# powersupply_vol6.net
KiCad netlist of a schematic drawn in EAGLE
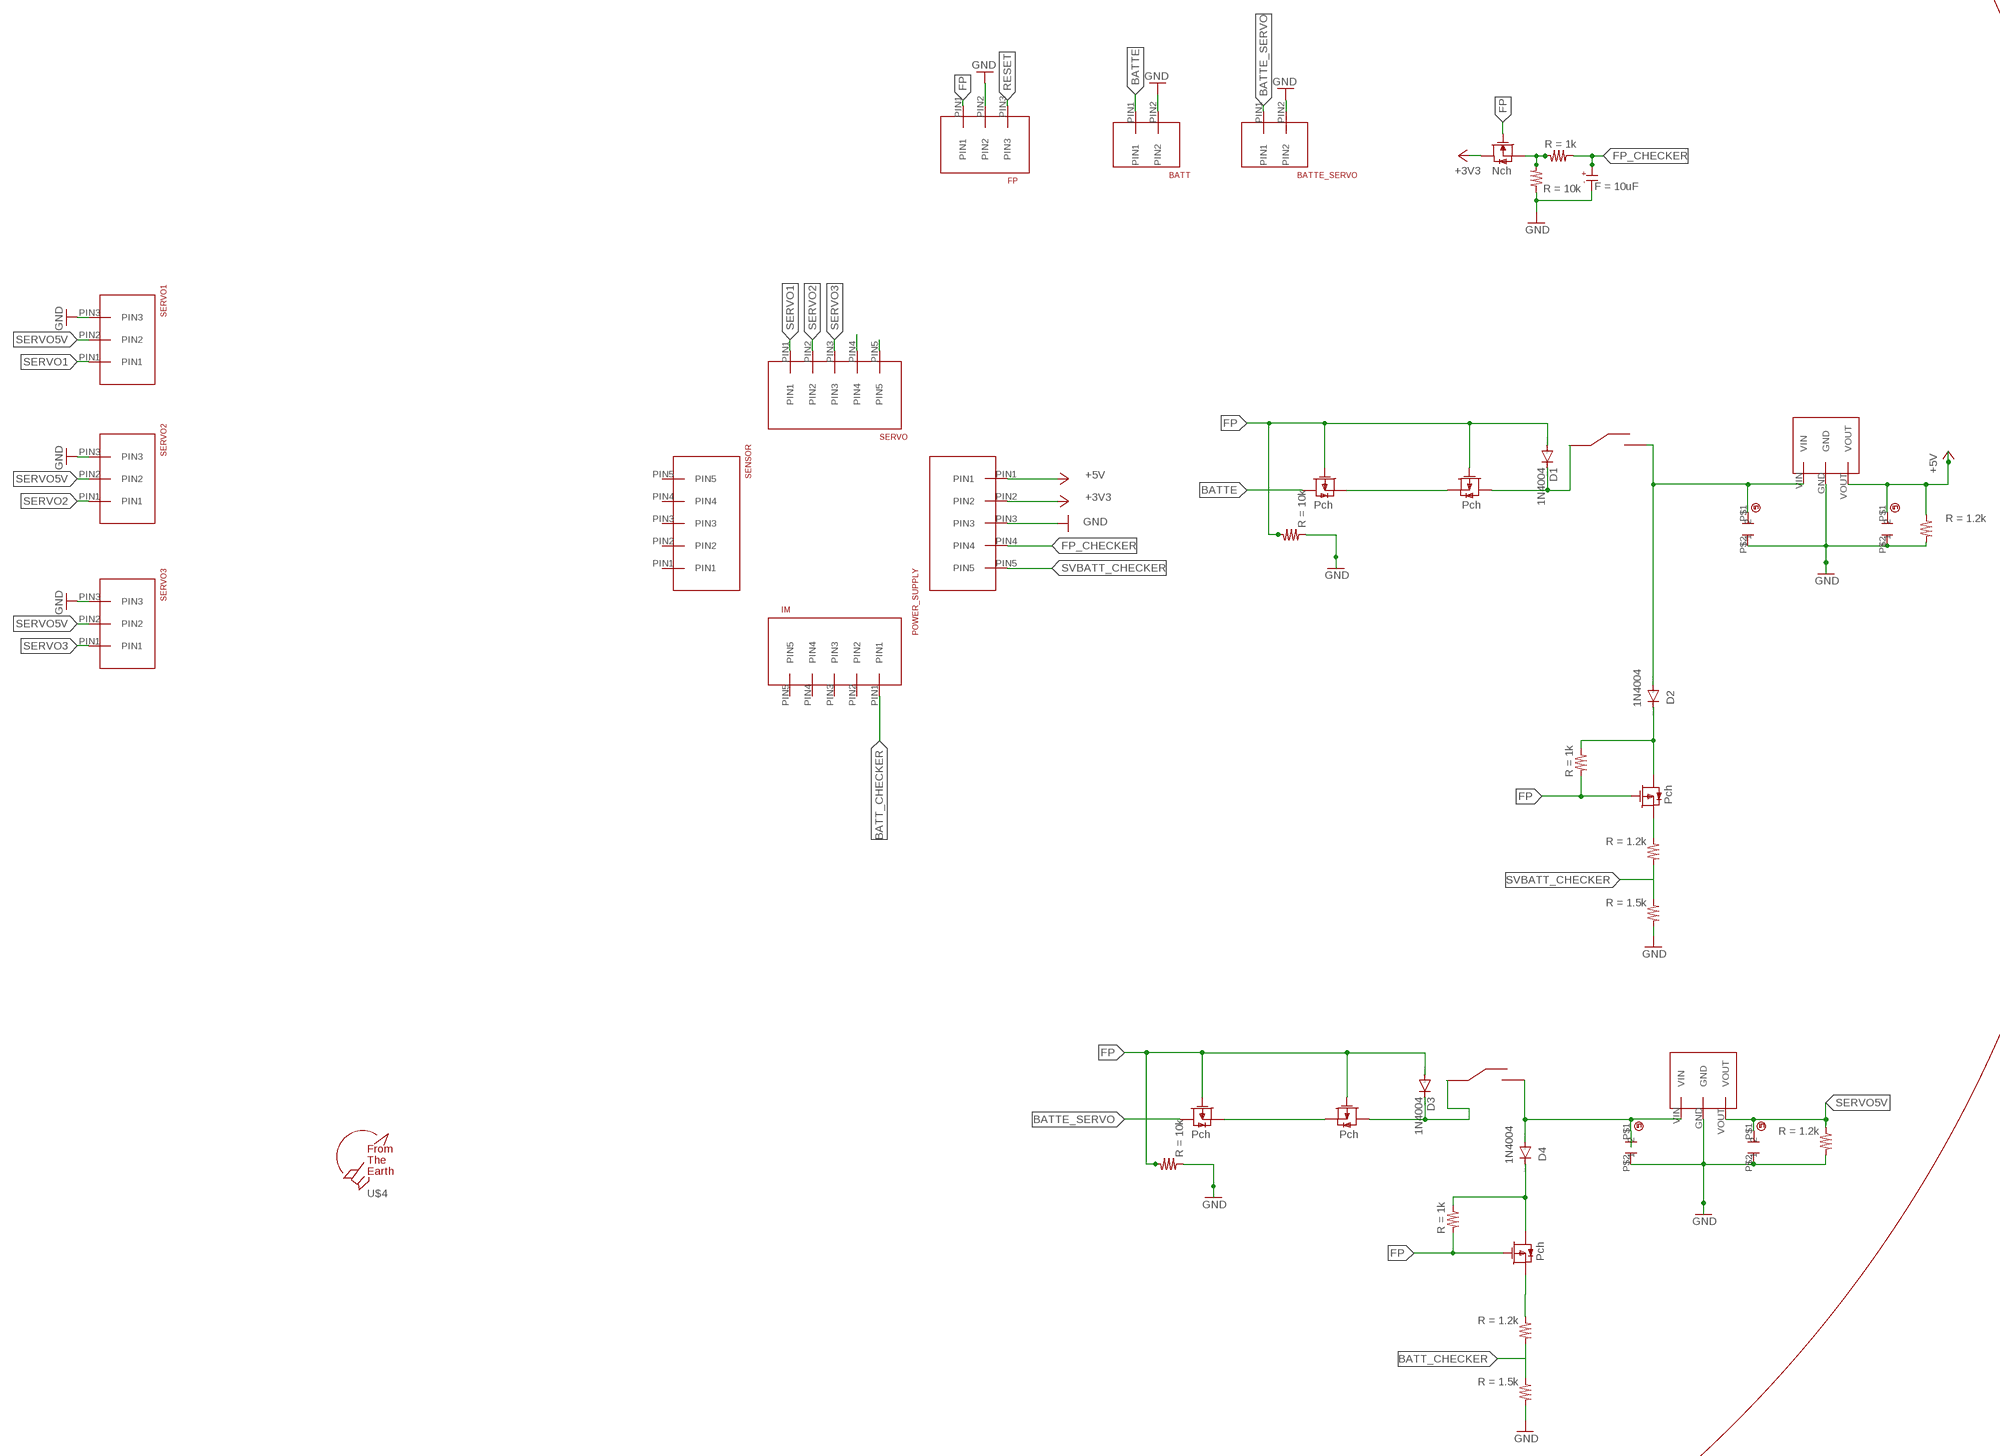
[diagram p0: schematic, sheet 1]

(export (version "E")
  (design (tool "Eeschema 10.0.6"))
  (components
    (comp (ref "BATT")
      (value "2PIN")
      (footprint "eagle-import:2PIN")
      (libsource (lib "eagle-import") (part "2PIN"))
    )
    (comp (ref "BATTE_SERVO")
      (value "2PIN")
      (footprint "eagle-import:2PIN")
      (libsource (lib "eagle-import") (part "2PIN"))
    )
    (comp (ref "C1")
      (value "CAPACITOR-ELECTROLYTIC_1")
      (footprint "eagle-import:CAPACITOR-ELECTROLYTIC_1")
      (fields (field (name "F") "10uF"))
      (libsource (lib "eagle-import") (part "CAPACITOR-ELECTROLYTIC_1"))
    )
    (comp (ref "CERAMIC_CAPACITOR3")
      (value "CERAMIC_CAPACITOR")
      (footprint "eagle-import:CERAMIC_CAPACITOR")
      (libsource (lib "eagle-import") (part "CERAMIC_CAPACITOR"))
    )
    (comp (ref "CERAMIC_CAPACITOR4")
      (value "CERAMIC_CAPACITOR")
      (footprint "eagle-import:CERAMIC_CAPACITOR")
      (libsource (lib "eagle-import") (part "CERAMIC_CAPACITOR"))
    )
    (comp (ref "CERAMIC_CAPACITOR5")
      (value "CERAMIC_CAPACITOR")
      (footprint "eagle-import:CERAMIC_CAPACITOR")
      (libsource (lib "eagle-import") (part "CERAMIC_CAPACITOR"))
    )
    (comp (ref "CERAMIC_CAPACITOR6")
      (value "CERAMIC_CAPACITOR")
      (footprint "eagle-import:CERAMIC_CAPACITOR")
      (libsource (lib "eagle-import") (part "CERAMIC_CAPACITOR"))
    )
    (comp (ref "D1")
      (value "1N4004")
      (footprint "eagle-import:DO41-10")
      (libsource (lib "eagle-import") (part "1N4004"))
    )
    (comp (ref "D2")
      (value "1N4004")
      (footprint "eagle-import:DO41-10")
      (libsource (lib "eagle-import") (part "1N4004"))
    )
    (comp (ref "D3")
      (value "1N4004")
      (footprint "eagle-import:DO41-10")
      (libsource (lib "eagle-import") (part "1N4004"))
    )
    (comp (ref "D4")
      (value "1N4004")
      (footprint "eagle-import:DO41-10")
      (libsource (lib "eagle-import") (part "1N4004"))
    )
    (comp (ref "FP")
      (value "3PIN")
      (footprint "eagle-import:3PIN")
      (libsource (lib "eagle-import") (part "3PIN"))
    )
    (comp (ref "IM")
      (value "5PIN")
      (footprint "eagle-import:5PIN")
      (libsource (lib "eagle-import") (part "5PIN"))
    )
    (comp (ref "POWER_SUPPLY")
      (value "5PIN")
      (footprint "eagle-import:5PIN")
      (libsource (lib "eagle-import") (part "5PIN"))
    )
    (comp (ref "R1")
      (value "1.5k")
      (footprint "eagle-import:REGISTER")
      (fields (field (name "R") "1.5k"))
      (libsource (lib "eagle-import") (part "RESISTER"))
    )
    (comp (ref "R2")
      (value "RESISTER")
      (footprint "eagle-import:REGISTER")
      (fields (field (name "R") "10k"))
      (libsource (lib "eagle-import") (part "RESISTER"))
    )
    (comp (ref "R3")
      (value "RESISTER")
      (footprint "eagle-import:REGISTER")
      (fields (field (name "R") "1.2k"))
      (libsource (lib "eagle-import") (part "RESISTER"))
    )
    (comp (ref "R4")
      (value "1.5k")
      (footprint "eagle-import:REGISTER")
      (fields (field (name "R") "1.5k"))
      (libsource (lib "eagle-import") (part "RESISTER"))
    )
    (comp (ref "R5")
      (value "RESISTER")
      (footprint "eagle-import:REGISTER")
      (fields (field (name "R") "10k"))
      (libsource (lib "eagle-import") (part "RESISTER"))
    )
    (comp (ref "R6")
      (value "RESISTER")
      (footprint "eagle-import:REGISTER")
      (fields (field (name "R") "1.2k"))
      (libsource (lib "eagle-import") (part "RESISTER"))
    )
    (comp (ref "R7")
      (value "RESISTER")
      (footprint "eagle-import:REGISTER")
      (fields (field (name "R") "1k"))
      (libsource (lib "eagle-import") (part "RESISTER"))
    )
    (comp (ref "R8")
      (value "RESISTER")
      (footprint "eagle-import:REGISTER")
      (fields (field (name "R") "1k"))
      (libsource (lib "eagle-import") (part "RESISTER"))
    )
    (comp (ref "R9")
      (value "RESISTER")
      (footprint "eagle-import:REGISTER")
      (fields (field (name "R") "10k"))
      (libsource (lib "eagle-import") (part "RESISTER"))
    )
    (comp (ref "R10")
      (value "RESISTER")
      (footprint "eagle-import:REGISTER")
      (fields (field (name "R") "1k"))
      (libsource (lib "eagle-import") (part "RESISTER"))
    )
    (comp (ref "R11")
      (value "RESISTER")
      (footprint "eagle-import:REGISTER")
      (fields (field (name "R") "1.2k"))
      (libsource (lib "eagle-import") (part "RESISTER"))
    )
    (comp (ref "R12")
      (value "RESISTER")
      (footprint "eagle-import:REGISTER")
      (fields (field (name "R") "1.2k"))
      (libsource (lib "eagle-import") (part "RESISTER"))
    )
    (comp (ref "SENSOR")
      (value "5PIN")
      (footprint "eagle-import:5PIN")
      (libsource (lib "eagle-import") (part "5PIN"))
    )
    (comp (ref "SERVO")
      (value "5PIN")
      (footprint "eagle-import:5PIN")
      (libsource (lib "eagle-import") (part "5PIN"))
    )
    (comp (ref "SERVO1")
      (value "3PIN")
      (footprint "eagle-import:3PIN")
      (libsource (lib "eagle-import") (part "3PIN"))
    )
    (comp (ref "SERVO2")
      (value "3PIN")
      (footprint "eagle-import:3PIN")
      (libsource (lib "eagle-import") (part "3PIN"))
    )
    (comp (ref "SERVO3")
      (value "3PIN")
      (footprint "eagle-import:3PIN")
      (libsource (lib "eagle-import") (part "3PIN"))
    )
    (comp (ref "U$1")
      (value "2SJ681-PCH")
      (footprint "eagle-import:2SJ681")
      (libsource (lib "eagle-import") (part "2SJ681-PCH"))
    )
    (comp (ref "U$2")
      (value "SLIDESWITCH")
      (footprint "eagle-import:SLIDESWITCH")
      (libsource (lib "eagle-import") (part "SLIDESWITCH"))
    )
    (comp (ref "U$3")
      (value "SLIDESWITCH")
      (footprint "eagle-import:SLIDESWITCH")
      (libsource (lib "eagle-import") (part "SLIDESWITCH"))
    )
    (comp (ref "U$4")
      (value "F.T.E.LOGO")
      (footprint "eagle-import:LOGO")
      (libsource (lib "eagle-import") (part "F.T.E.LOGO"))
    )
    (comp (ref "U$5")
      (value "2SJ681-PCH")
      (footprint "eagle-import:2SJ681")
      (libsource (lib "eagle-import") (part "2SJ681-PCH"))
    )
    (comp (ref "U$8")
      (value "2SK4017-NCH")
      (footprint "eagle-import:2SK4017")
      (libsource (lib "eagle-import") (part "2SK4017-NCH"))
    )
    (comp (ref "U$12")
      (value "2SJ681-PCH")
      (footprint "eagle-import:2SJ681")
      (libsource (lib "eagle-import") (part "2SJ681-PCH"))
    )
    (comp (ref "U$13")
      (value "2SJ681-PCH")
      (footprint "eagle-import:2SJ681")
      (libsource (lib "eagle-import") (part "2SJ681-PCH"))
    )
    (comp (ref "U$14")
      (value "M78AR05-1")
      (footprint "eagle-import:M78AR05-1")
      (libsource (lib "eagle-import") (part "M78AR05-1"))
    )
    (comp (ref "U$30")
      (value "2SJ681-PCH")
      (footprint "eagle-import:2SJ681")
      (libsource (lib "eagle-import") (part "2SJ681-PCH"))
    )
    (comp (ref "U$31")
      (value "2SJ681-PCH")
      (footprint "eagle-import:2SJ681")
      (libsource (lib "eagle-import") (part "2SJ681-PCH"))
    )
    (comp (ref "U$32")
      (value "M78AR05-1")
      (footprint "eagle-import:M78AR05-1")
      (libsource (lib "eagle-import") (part "M78AR05-1"))
    )
  )
  (nets
    (net (code "1") (name "+3V3") (class "Default")
      (node (ref "POWER_SUPPLY") (pin "PIN2") (pinfunction "PIN2_PIN2") (pintype "bidirectional"))
      (node (ref "U$8") (pin "DRAIN") (pinfunction "DRAIN_DRAIN") (pintype "bidirectional"))
    )
    (net (code "2") (name "+5V") (class "Default")
      (node (ref "CERAMIC_CAPACITOR5") (pin "P$1") (pinfunction "1_P$1") (pintype "bidirectional"))
      (node (ref "POWER_SUPPLY") (pin "PIN1") (pinfunction "PIN1_PIN1") (pintype "bidirectional"))
      (node (ref "R11") (pin "A") (pinfunction "A_A") (pintype "bidirectional"))
      (node (ref "U$32") (pin "VOUT") (pinfunction "VOUT_VOUT") (pintype "bidirectional"))
    )
    (net (code "3") (name "BATTE") (class "Default")
      (node (ref "BATT") (pin "PIN1") (pinfunction "PIN1_PIN1") (pintype "bidirectional"))
      (node (ref "U$30") (pin "DRAIN") (pinfunction "DRAIN_DRAIN") (pintype "bidirectional"))
    )
    (net (code "4") (name "BATTE_SERVO") (class "Default")
      (node (ref "BATTE_SERVO") (pin "PIN1") (pinfunction "PIN1_PIN1") (pintype "bidirectional"))
      (node (ref "U$13") (pin "DRAIN") (pinfunction "DRAIN_DRAIN") (pintype "bidirectional"))
    )
    (net (code "5") (name "BATT_CHECKER") (class "Default")
      (node (ref "IM") (pin "PIN1") (pinfunction "PIN1_PIN1") (pintype "bidirectional"))
      (node (ref "R1") (pin "A") (pinfunction "A_A") (pintype "bidirectional"))
      (node (ref "R3") (pin "B") (pinfunction "B_B") (pintype "bidirectional"))
    )
    (net (code "6") (name "FP") (class "Default")
      (node (ref "D1") (pin "A") (pinfunction "A_A") (pintype "passive"))
      (node (ref "D3") (pin "A") (pinfunction "A_A") (pintype "passive"))
      (node (ref "FP") (pin "PIN1") (pinfunction "PIN1_PIN1") (pintype "bidirectional"))
      (node (ref "R2") (pin "B") (pinfunction "B_B") (pintype "bidirectional"))
      (node (ref "R5") (pin "B") (pinfunction "B_B") (pintype "bidirectional"))
      (node (ref "R7") (pin "B") (pinfunction "B_B") (pintype "bidirectional"))
      (node (ref "R8") (pin "B") (pinfunction "B_B") (pintype "bidirectional"))
      (node (ref "U$1") (pin "GATE") (pinfunction "GATE_GATE") (pintype "bidirectional"))
      (node (ref "U$12") (pin "GATE") (pinfunction "GATE_GATE") (pintype "bidirectional"))
      (node (ref "U$13") (pin "GATE") (pinfunction "GATE_GATE") (pintype "bidirectional"))
      (node (ref "U$30") (pin "GATE") (pinfunction "GATE_GATE") (pintype "bidirectional"))
      (node (ref "U$31") (pin "GATE") (pinfunction "GATE_GATE") (pintype "bidirectional"))
      (node (ref "U$5") (pin "GATE") (pinfunction "GATE_GATE") (pintype "bidirectional"))
      (node (ref "U$8") (pin "GATE") (pinfunction "GATE_GATE") (pintype "bidirectional"))
    )
    (net (code "7") (name "FP_CHECKER") (class "Default")
      (node (ref "C1") (pin "KS") (pinfunction "KS_KS") (pintype "bidirectional"))
      (node (ref "POWER_SUPPLY") (pin "PIN4") (pinfunction "PIN4_PIN4") (pintype "bidirectional"))
      (node (ref "R10") (pin "A") (pinfunction "A_A") (pintype "bidirectional"))
    )
    (net (code "8") (name "GND") (class "Default")
      (node (ref "BATT") (pin "PIN2") (pinfunction "PIN2_PIN2") (pintype "bidirectional"))
      (node (ref "BATTE_SERVO") (pin "PIN2") (pinfunction "PIN2_PIN2") (pintype "bidirectional"))
      (node (ref "C1") (pin "AN") (pinfunction "AN_AN") (pintype "bidirectional"))
      (node (ref "CERAMIC_CAPACITOR3") (pin "P$2") (pinfunction "2_P$2") (pintype "bidirectional"))
      (node (ref "CERAMIC_CAPACITOR4") (pin "P$2") (pinfunction "2_P$2") (pintype "bidirectional"))
      (node (ref "CERAMIC_CAPACITOR5") (pin "P$2") (pinfunction "2_P$2") (pintype "bidirectional"))
      (node (ref "CERAMIC_CAPACITOR6") (pin "P$2") (pinfunction "2_P$2") (pintype "bidirectional"))
      (node (ref "FP") (pin "PIN2") (pinfunction "PIN2_PIN2") (pintype "bidirectional"))
      (node (ref "POWER_SUPPLY") (pin "PIN3") (pinfunction "PIN3_PIN3") (pintype "bidirectional"))
      (node (ref "R1") (pin "B") (pinfunction "B_B") (pintype "bidirectional"))
      (node (ref "R11") (pin "B") (pinfunction "B_B") (pintype "bidirectional"))
      (node (ref "R12") (pin "B") (pinfunction "B_B") (pintype "bidirectional"))
      (node (ref "R2") (pin "A") (pinfunction "A_A") (pintype "bidirectional"))
      (node (ref "R4") (pin "B") (pinfunction "B_B") (pintype "bidirectional"))
      (node (ref "R5") (pin "A") (pinfunction "A_A") (pintype "bidirectional"))
      (node (ref "R9") (pin "A") (pinfunction "A_A") (pintype "bidirectional"))
      (node (ref "SERVO1") (pin "PIN3") (pinfunction "PIN3_PIN3") (pintype "bidirectional"))
      (node (ref "SERVO2") (pin "PIN3") (pinfunction "PIN3_PIN3") (pintype "bidirectional"))
      (node (ref "SERVO3") (pin "PIN3") (pinfunction "PIN3_PIN3") (pintype "bidirectional"))
      (node (ref "U$14") (pin "GND") (pinfunction "GND_GND") (pintype "bidirectional"))
      (node (ref "U$32") (pin "GND") (pinfunction "GND_GND") (pintype "bidirectional"))
    )
    (net (code "9") (name "Net-(CERAMIC_CAPACITOR4-1)") (class "Default")
      (node (ref "CERAMIC_CAPACITOR4") (pin "P$1") (pinfunction "1_P$1") (pintype "bidirectional"))
      (node (ref "D4") (pin "A") (pinfunction "A_A") (pintype "passive"))
      (node (ref "U$14") (pin "VIN") (pinfunction "VIN_VIN") (pintype "bidirectional"))
      (node (ref "U$3") (pin "C") (pinfunction "C_C") (pintype "bidirectional"))
    )
    (net (code "10") (name "Net-(CERAMIC_CAPACITOR6-1)") (class "Default")
      (node (ref "CERAMIC_CAPACITOR6") (pin "P$1") (pinfunction "1_P$1") (pintype "bidirectional"))
      (node (ref "D2") (pin "A") (pinfunction "A_A") (pintype "passive"))
      (node (ref "U$2") (pin "C") (pinfunction "C_C") (pintype "bidirectional"))
      (node (ref "U$32") (pin "VIN") (pinfunction "VIN_VIN") (pintype "bidirectional"))
    )
    (net (code "11") (name "Net-(D1-PadC)") (class "Default")
      (node (ref "D1") (pin "C") (pinfunction "C_C") (pintype "passive"))
      (node (ref "U$2") (pin "A") (pinfunction "A_A") (pintype "bidirectional"))
      (node (ref "U$31") (pin "DRAIN") (pinfunction "DRAIN_DRAIN") (pintype "bidirectional"))
    )
    (net (code "12") (name "Net-(D2-PadC)") (class "Default")
      (node (ref "D2") (pin "C") (pinfunction "C_C") (pintype "passive"))
      (node (ref "R7") (pin "A") (pinfunction "A_A") (pintype "bidirectional"))
      (node (ref "U$1") (pin "DRAIN") (pinfunction "DRAIN_DRAIN") (pintype "bidirectional"))
    )
    (net (code "13") (name "Net-(D3-PadC)") (class "Default")
      (node (ref "D3") (pin "C") (pinfunction "C_C") (pintype "passive"))
      (node (ref "U$12") (pin "DRAIN") (pinfunction "DRAIN_DRAIN") (pintype "bidirectional"))
      (node (ref "U$3") (pin "A") (pinfunction "A_A") (pintype "bidirectional"))
    )
    (net (code "14") (name "Net-(D4-PadC)") (class "Default")
      (node (ref "D4") (pin "C") (pinfunction "C_C") (pintype "passive"))
      (node (ref "R8") (pin "A") (pinfunction "A_A") (pintype "bidirectional"))
      (node (ref "U$5") (pin "DRAIN") (pinfunction "DRAIN_DRAIN") (pintype "bidirectional"))
    )
    (net (code "15") (name "Net-(R3-PadA)") (class "Default")
      (node (ref "R3") (pin "A") (pinfunction "A_A") (pintype "bidirectional"))
      (node (ref "U$5") (pin "SOURCE") (pinfunction "SOURCE_SOURCE") (pintype "bidirectional"))
    )
    (net (code "16") (name "Net-(R6-PadA)") (class "Default")
      (node (ref "R6") (pin "A") (pinfunction "A_A") (pintype "bidirectional"))
      (node (ref "U$1") (pin "SOURCE") (pinfunction "SOURCE_SOURCE") (pintype "bidirectional"))
    )
    (net (code "17") (name "Net-(R10-PadB)") (class "Default")
      (node (ref "R10") (pin "B") (pinfunction "B_B") (pintype "bidirectional"))
      (node (ref "R9") (pin "B") (pinfunction "B_B") (pintype "bidirectional"))
      (node (ref "U$8") (pin "SOURCE") (pinfunction "SOURCE_SOURCE") (pintype "bidirectional"))
    )
    (net (code "18") (name "Net-(U$12-PadSOURCE)") (class "Default")
      (node (ref "U$12") (pin "SOURCE") (pinfunction "SOURCE_SOURCE") (pintype "bidirectional"))
      (node (ref "U$13") (pin "SOURCE") (pinfunction "SOURCE_SOURCE") (pintype "bidirectional"))
    )
    (net (code "19") (name "Net-(U$30-PadSOURCE)") (class "Default")
      (node (ref "U$30") (pin "SOURCE") (pinfunction "SOURCE_SOURCE") (pintype "bidirectional"))
      (node (ref "U$31") (pin "SOURCE") (pinfunction "SOURCE_SOURCE") (pintype "bidirectional"))
    )
    (net (code "20") (name "RESET") (class "Default")
      (node (ref "FP") (pin "PIN3") (pinfunction "PIN3_PIN3") (pintype "bidirectional"))
    )
    (net (code "21") (name "SERVO1") (class "Default")
      (node (ref "SERVO") (pin "PIN1") (pinfunction "PIN1_PIN1") (pintype "bidirectional"))
      (node (ref "SERVO1") (pin "PIN1") (pinfunction "PIN1_PIN1") (pintype "bidirectional"))
    )
    (net (code "22") (name "SERVO2") (class "Default")
      (node (ref "SERVO") (pin "PIN2") (pinfunction "PIN2_PIN2") (pintype "bidirectional"))
      (node (ref "SERVO2") (pin "PIN1") (pinfunction "PIN1_PIN1") (pintype "bidirectional"))
    )
    (net (code "23") (name "SERVO3") (class "Default")
      (node (ref "SERVO") (pin "PIN3") (pinfunction "PIN3_PIN3") (pintype "bidirectional"))
      (node (ref "SERVO3") (pin "PIN1") (pinfunction "PIN1_PIN1") (pintype "bidirectional"))
    )
    (net (code "24") (name "SERVO5V") (class "Default")
      (node (ref "CERAMIC_CAPACITOR3") (pin "P$1") (pinfunction "1_P$1") (pintype "bidirectional"))
      (node (ref "R12") (pin "A") (pinfunction "A_A") (pintype "bidirectional"))
      (node (ref "SERVO1") (pin "PIN2") (pinfunction "PIN2_PIN2") (pintype "bidirectional"))
      (node (ref "SERVO2") (pin "PIN2") (pinfunction "PIN2_PIN2") (pintype "bidirectional"))
      (node (ref "SERVO3") (pin "PIN2") (pinfunction "PIN2_PIN2") (pintype "bidirectional"))
      (node (ref "U$14") (pin "VOUT") (pinfunction "VOUT_VOUT") (pintype "bidirectional"))
    )
    (net (code "25") (name "SVBATT_CHECKER") (class "Default")
      (node (ref "POWER_SUPPLY") (pin "PIN5") (pinfunction "PIN5_PIN5") (pintype "bidirectional"))
      (node (ref "R4") (pin "A") (pinfunction "A_A") (pintype "bidirectional"))
      (node (ref "R6") (pin "B") (pinfunction "B_B") (pintype "bidirectional"))
    )
    (net (code "26") (name "unconnected-(IM-PadPIN2)") (class "Default")
      (node (ref "IM") (pin "PIN2") (pinfunction "PIN2_PIN2") (pintype "bidirectional"))
    )
    (net (code "27") (name "unconnected-(IM-PadPIN3)") (class "Default")
      (node (ref "IM") (pin "PIN3") (pinfunction "PIN3_PIN3") (pintype "bidirectional"))
    )
    (net (code "28") (name "unconnected-(IM-PadPIN4)") (class "Default")
      (node (ref "IM") (pin "PIN4") (pinfunction "PIN4_PIN4") (pintype "bidirectional"))
    )
    (net (code "29") (name "unconnected-(IM-PadPIN5)") (class "Default")
      (node (ref "IM") (pin "PIN5") (pinfunction "PIN5_PIN5") (pintype "bidirectional"))
    )
    (net (code "30") (name "unconnected-(SENSOR-PadPIN1)") (class "Default")
      (node (ref "SENSOR") (pin "PIN1") (pinfunction "PIN1_PIN1") (pintype "bidirectional"))
    )
    (net (code "31") (name "unconnected-(SENSOR-PadPIN2)") (class "Default")
      (node (ref "SENSOR") (pin "PIN2") (pinfunction "PIN2_PIN2") (pintype "bidirectional"))
    )
    (net (code "32") (name "unconnected-(SENSOR-PadPIN3)") (class "Default")
      (node (ref "SENSOR") (pin "PIN3") (pinfunction "PIN3_PIN3") (pintype "bidirectional"))
    )
    (net (code "33") (name "unconnected-(SENSOR-PadPIN4)") (class "Default")
      (node (ref "SENSOR") (pin "PIN4") (pinfunction "PIN4_PIN4") (pintype "bidirectional"))
    )
    (net (code "34") (name "unconnected-(SENSOR-PadPIN5)") (class "Default")
      (node (ref "SENSOR") (pin "PIN5") (pinfunction "PIN5_PIN5") (pintype "bidirectional"))
    )
    (net (code "35") (name "unconnected-(SERVO-PadPIN4)") (class "Default")
      (node (ref "SERVO") (pin "PIN4") (pinfunction "PIN4_PIN4") (pintype "bidirectional"))
    )
    (net (code "36") (name "unconnected-(SERVO-PadPIN5)") (class "Default")
      (node (ref "SERVO") (pin "PIN5") (pinfunction "PIN5_PIN5") (pintype "bidirectional"))
    )
    (net (code "37") (name "unconnected-(U$2-PadB)") (class "Default")
      (node (ref "U$2") (pin "B") (pinfunction "B_B") (pintype "bidirectional"))
    )
    (net (code "38") (name "unconnected-(U$3-PadB)") (class "Default")
      (node (ref "U$3") (pin "B") (pinfunction "B_B") (pintype "bidirectional"))
    )
  )
)
